# Data_Board_4_Panel.net
KiCad netlist of a schematic drawn in EAGLE
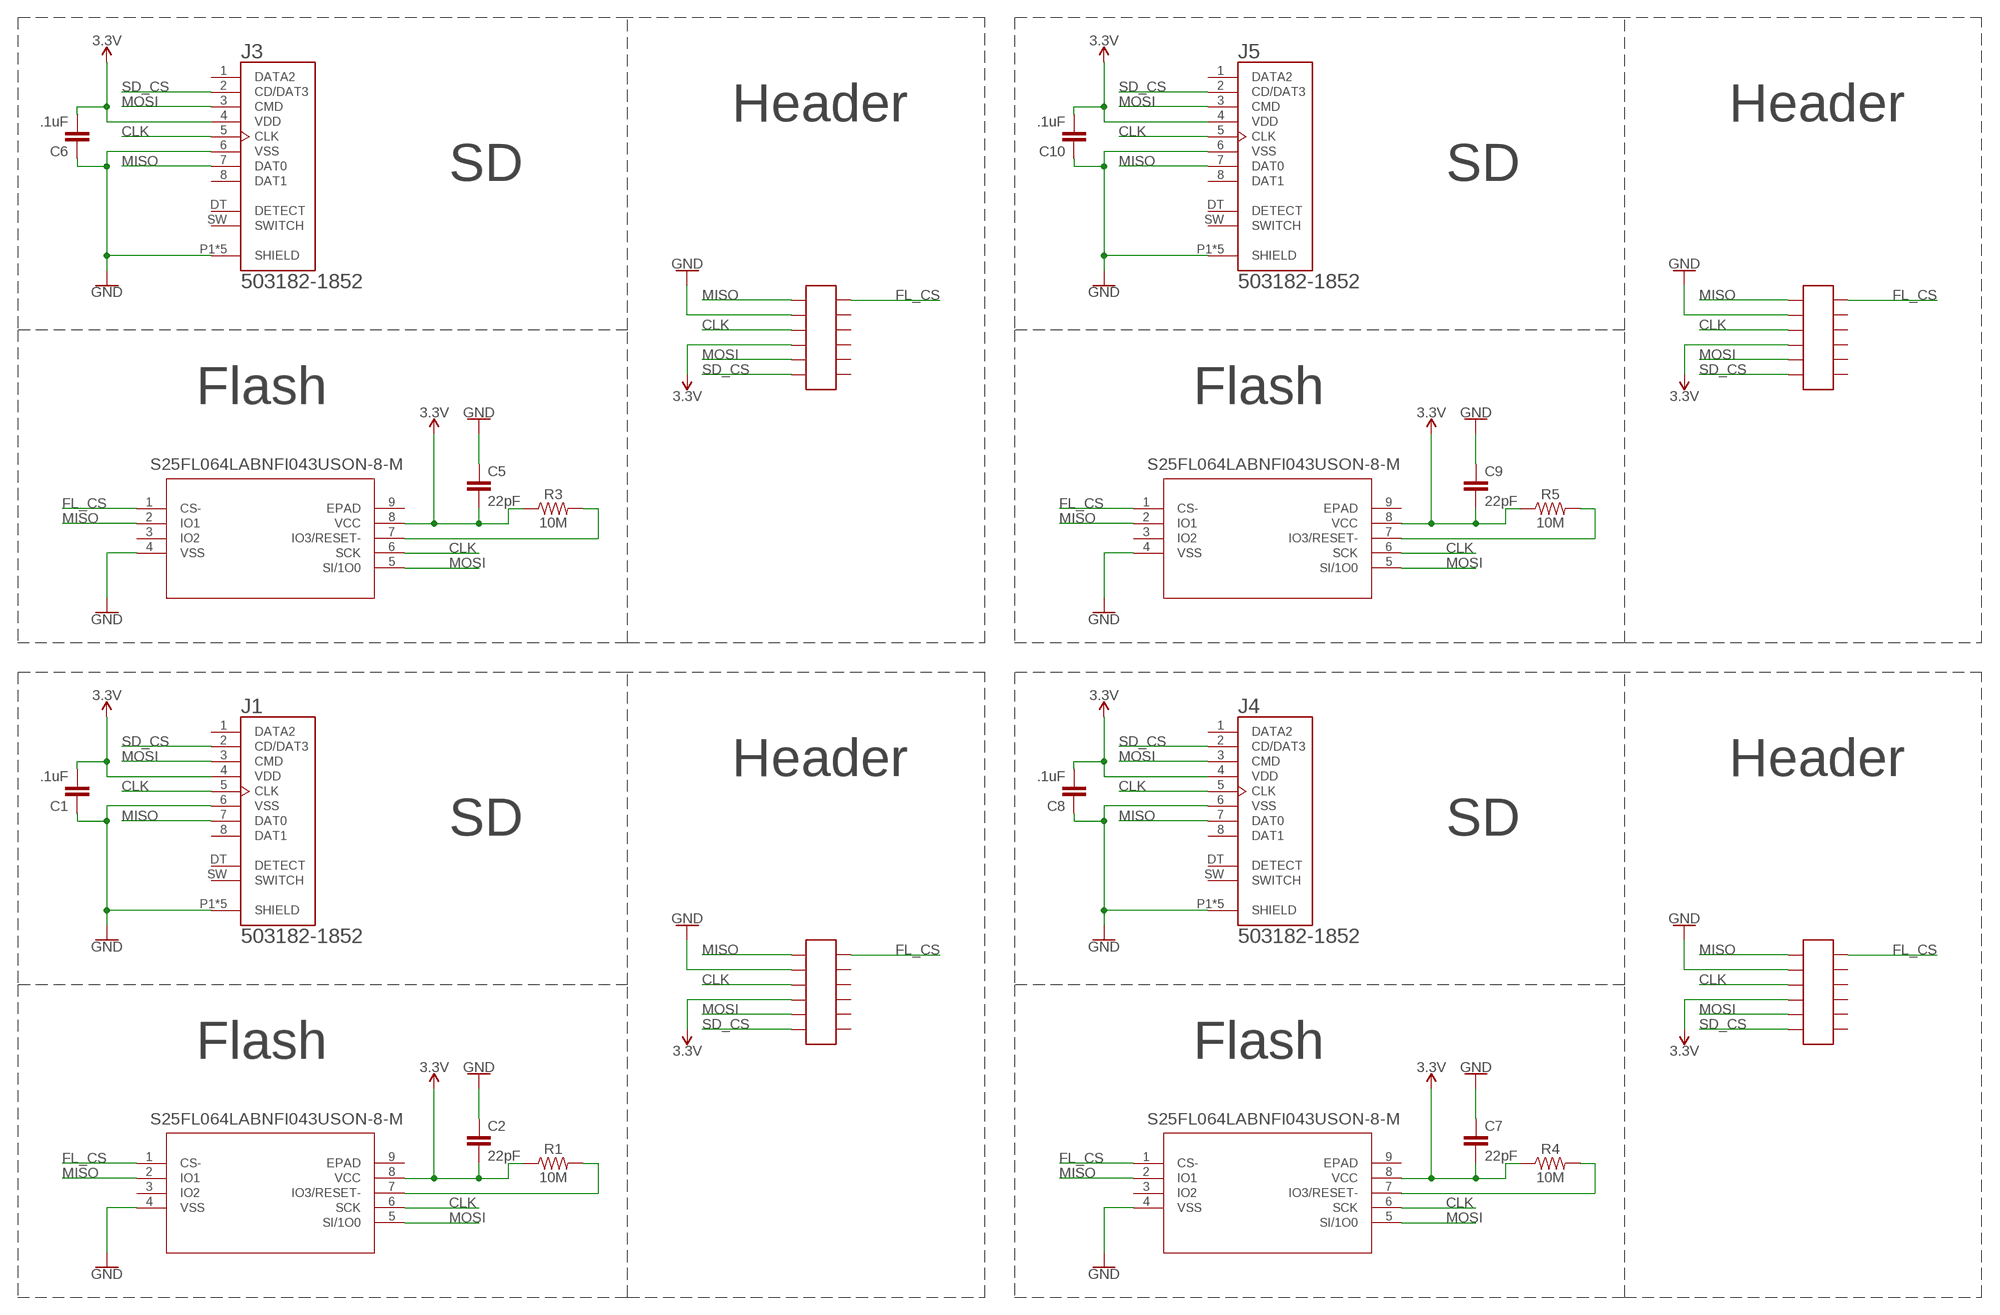
[diagram p0: schematic, sheet 1]

(export (version "E")
  (design (tool "Eeschema 10.0.6"))
  (components
    (comp (ref "C1")
      (value ".1uF")
      (footprint "eagle-import:0603")
      (libsource (lib "eagle-import") (part "10NF-0603-50V-10%"))
    )
    (comp (ref "C2")
      (value "22pF")
      (footprint "eagle-import:0603")
      (libsource (lib "eagle-import") (part "10NF-0603-50V-10%"))
    )
    (comp (ref "C5")
      (value "22pF")
      (footprint "eagle-import:0603")
      (libsource (lib "eagle-import") (part "10NF-0603-50V-10%"))
    )
    (comp (ref "C6")
      (value ".1uF")
      (footprint "eagle-import:0603")
      (libsource (lib "eagle-import") (part "10NF-0603-50V-10%"))
    )
    (comp (ref "C7")
      (value "22pF")
      (footprint "eagle-import:0603")
      (libsource (lib "eagle-import") (part "10NF-0603-50V-10%"))
    )
    (comp (ref "C8")
      (value ".1uF")
      (footprint "eagle-import:0603")
      (libsource (lib "eagle-import") (part "10NF-0603-50V-10%"))
    )
    (comp (ref "C9")
      (value "22pF")
      (footprint "eagle-import:0603")
      (libsource (lib "eagle-import") (part "10NF-0603-50V-10%"))
    )
    (comp (ref "C10")
      (value ".1uF")
      (footprint "eagle-import:0603")
      (libsource (lib "eagle-import") (part "10NF-0603-50V-10%"))
    )
    (comp (ref "J1")
      (value "503182-1852")
      (footprint "eagle-import:MOLEX_503182-1852")
      (fields
        (field (name "DIGI-KEY_PART_NUMBER") "WM12834CT-ND")
        (field (name "MF") "Molex")
        (field (name "MP") "5031821852")
      )
      (libsource (lib "eagle-import") (part "503182-1852"))
    )
    (comp (ref "J3")
      (value "503182-1852")
      (footprint "eagle-import:MOLEX_503182-1852")
      (fields
        (field (name "DIGI-KEY_PART_NUMBER") "WM12834CT-ND")
        (field (name "MF") "Molex")
        (field (name "MP") "5031821852")
      )
      (libsource (lib "eagle-import") (part "503182-1852"))
    )
    (comp (ref "J4")
      (value "503182-1852")
      (footprint "eagle-import:MOLEX_503182-1852")
      (fields
        (field (name "DIGI-KEY_PART_NUMBER") "WM12834CT-ND")
        (field (name "MF") "Molex")
        (field (name "MP") "5031821852")
      )
      (libsource (lib "eagle-import") (part "503182-1852"))
    )
    (comp (ref "J5")
      (value "503182-1852")
      (footprint "eagle-import:MOLEX_503182-1852")
      (fields
        (field (name "DIGI-KEY_PART_NUMBER") "WM12834CT-ND")
        (field (name "MF") "Molex")
        (field (name "MP") "5031821852")
      )
      (libsource (lib "eagle-import") (part "503182-1852"))
    )
    (comp (ref "R1")
      (value "10M")
      (footprint "eagle-import:0603")
      (libsource (lib "eagle-import") (part "220KOHM-0603-1/10W-1%"))
    )
    (comp (ref "R3")
      (value "10M")
      (footprint "eagle-import:0603")
      (libsource (lib "eagle-import") (part "220KOHM-0603-1/10W-1%"))
    )
    (comp (ref "R4")
      (value "10M")
      (footprint "eagle-import:0603")
      (libsource (lib "eagle-import") (part "220KOHM-0603-1/10W-1%"))
    )
    (comp (ref "R5")
      (value "10M")
      (footprint "eagle-import:0603")
      (libsource (lib "eagle-import") (part "220KOHM-0603-1/10W-1%"))
    )
    (comp (ref "U$1")
      (value "12POS_HEADER")
      (footprint "eagle-import:12POS_HEADER")
      (libsource (lib "eagle-import") (part "12POS_HEADER"))
    )
    (comp (ref "U$3")
      (value "12POS_HEADER")
      (footprint "eagle-import:12POS_HEADER")
      (libsource (lib "eagle-import") (part "12POS_HEADER"))
    )
    (comp (ref "U$4")
      (value "12POS_HEADER")
      (footprint "eagle-import:12POS_HEADER")
      (libsource (lib "eagle-import") (part "12POS_HEADER"))
    )
    (comp (ref "U$5")
      (value "12POS_HEADER")
      (footprint "eagle-import:12POS_HEADER")
      (libsource (lib "eagle-import") (part "12POS_HEADER"))
    )
    (comp (ref "U1")
      (value "S25FL064LABNFI043USON-8-M")
      (footprint "eagle-import:USON-8-M")
      (fields
        (field (name "MANUFACTURER_PART_NUMBER") "S25FL064LABNFI043")
        (field (name "COPYRIGHT") "Copyright (C) 2018 Accelerated Designs. All rights reserved")
      )
      (libsource (lib "eagle-import") (part "S25FL064LABNFI043USON-8-M"))
    )
    (comp (ref "U3")
      (value "S25FL064LABNFI043USON-8-M")
      (footprint "eagle-import:USON-8-M")
      (fields
        (field (name "MANUFACTURER_PART_NUMBER") "S25FL064LABNFI043")
        (field (name "COPYRIGHT") "Copyright (C) 2018 Accelerated Designs. All rights reserved")
      )
      (libsource (lib "eagle-import") (part "S25FL064LABNFI043USON-8-M"))
    )
    (comp (ref "U4")
      (value "S25FL064LABNFI043USON-8-M")
      (footprint "eagle-import:USON-8-M")
      (fields
        (field (name "MANUFACTURER_PART_NUMBER") "S25FL064LABNFI043")
        (field (name "COPYRIGHT") "Copyright (C) 2018 Accelerated Designs. All rights reserved")
      )
      (libsource (lib "eagle-import") (part "S25FL064LABNFI043USON-8-M"))
    )
    (comp (ref "U5")
      (value "S25FL064LABNFI043USON-8-M")
      (footprint "eagle-import:USON-8-M")
      (fields
        (field (name "MANUFACTURER_PART_NUMBER") "S25FL064LABNFI043")
        (field (name "COPYRIGHT") "Copyright (C) 2018 Accelerated Designs. All rights reserved")
      )
      (libsource (lib "eagle-import") (part "S25FL064LABNFI043USON-8-M"))
    )
  )
  (nets
    (net (code "1") (name "/CLK") (class "Default")
      (node (ref "J1") (pin "5") (pinfunction "CLK_5") (pintype "bidirectional"))
      (node (ref "J3") (pin "5") (pinfunction "CLK_5") (pintype "bidirectional"))
      (node (ref "J4") (pin "5") (pinfunction "CLK_5") (pintype "bidirectional"))
      (node (ref "J5") (pin "5") (pinfunction "CLK_5") (pintype "bidirectional"))
      (node (ref "U$1") (pin "P$3") (pinfunction "P$3_P$3") (pintype "bidirectional"))
      (node (ref "U$3") (pin "P$3") (pinfunction "P$3_P$3") (pintype "bidirectional"))
      (node (ref "U$4") (pin "P$3") (pinfunction "P$3_P$3") (pintype "bidirectional"))
      (node (ref "U$5") (pin "P$3") (pinfunction "P$3_P$3") (pintype "bidirectional"))
      (node (ref "U1") (pin "6") (pinfunction "SCK_6") (pintype "passive"))
      (node (ref "U3") (pin "6") (pinfunction "SCK_6") (pintype "passive"))
      (node (ref "U4") (pin "6") (pinfunction "SCK_6") (pintype "passive"))
      (node (ref "U5") (pin "6") (pinfunction "SCK_6") (pintype "passive"))
    )
    (net (code "2") (name "/FL_CS") (class "Default")
      (node (ref "U$1") (pin "P$12") (pinfunction "P$12_P$12") (pintype "bidirectional"))
      (node (ref "U$3") (pin "P$12") (pinfunction "P$12_P$12") (pintype "bidirectional"))
      (node (ref "U$4") (pin "P$12") (pinfunction "P$12_P$12") (pintype "bidirectional"))
      (node (ref "U$5") (pin "P$12") (pinfunction "P$12_P$12") (pintype "bidirectional"))
      (node (ref "U1") (pin "1") (pinfunction "CS-_1") (pintype "passive"))
      (node (ref "U3") (pin "1") (pinfunction "CS-_1") (pintype "passive"))
      (node (ref "U4") (pin "1") (pinfunction "CS-_1") (pintype "passive"))
      (node (ref "U5") (pin "1") (pinfunction "CS-_1") (pintype "passive"))
    )
    (net (code "3") (name "/MISO") (class "Default")
      (node (ref "J1") (pin "7") (pinfunction "DAT0_7") (pintype "bidirectional"))
      (node (ref "J3") (pin "7") (pinfunction "DAT0_7") (pintype "bidirectional"))
      (node (ref "J4") (pin "7") (pinfunction "DAT0_7") (pintype "bidirectional"))
      (node (ref "J5") (pin "7") (pinfunction "DAT0_7") (pintype "bidirectional"))
      (node (ref "U$1") (pin "P$1") (pinfunction "P$1_P$1") (pintype "bidirectional"))
      (node (ref "U$3") (pin "P$1") (pinfunction "P$1_P$1") (pintype "bidirectional"))
      (node (ref "U$4") (pin "P$1") (pinfunction "P$1_P$1") (pintype "bidirectional"))
      (node (ref "U$5") (pin "P$1") (pinfunction "P$1_P$1") (pintype "bidirectional"))
      (node (ref "U1") (pin "2") (pinfunction "IO1_2") (pintype "bidirectional"))
      (node (ref "U3") (pin "2") (pinfunction "IO1_2") (pintype "bidirectional"))
      (node (ref "U4") (pin "2") (pinfunction "IO1_2") (pintype "bidirectional"))
      (node (ref "U5") (pin "2") (pinfunction "IO1_2") (pintype "bidirectional"))
    )
    (net (code "4") (name "/MOSI") (class "Default")
      (node (ref "J1") (pin "3") (pinfunction "CMD_3") (pintype "bidirectional"))
      (node (ref "J3") (pin "3") (pinfunction "CMD_3") (pintype "bidirectional"))
      (node (ref "J4") (pin "3") (pinfunction "CMD_3") (pintype "bidirectional"))
      (node (ref "J5") (pin "3") (pinfunction "CMD_3") (pintype "bidirectional"))
      (node (ref "U$1") (pin "P$5") (pinfunction "P$5_P$5") (pintype "bidirectional"))
      (node (ref "U$3") (pin "P$5") (pinfunction "P$5_P$5") (pintype "bidirectional"))
      (node (ref "U$4") (pin "P$5") (pinfunction "P$5_P$5") (pintype "bidirectional"))
      (node (ref "U$5") (pin "P$5") (pinfunction "P$5_P$5") (pintype "bidirectional"))
      (node (ref "U1") (pin "5") (pinfunction "SI/1O0_5") (pintype "passive"))
      (node (ref "U3") (pin "5") (pinfunction "SI/1O0_5") (pintype "passive"))
      (node (ref "U4") (pin "5") (pinfunction "SI/1O0_5") (pintype "passive"))
      (node (ref "U5") (pin "5") (pinfunction "SI/1O0_5") (pintype "passive"))
    )
    (net (code "5") (name "/SD_CS") (class "Default")
      (node (ref "J1") (pin "2") (pinfunction "CD/DAT3_2") (pintype "bidirectional"))
      (node (ref "J3") (pin "2") (pinfunction "CD/DAT3_2") (pintype "bidirectional"))
      (node (ref "J4") (pin "2") (pinfunction "CD/DAT3_2") (pintype "bidirectional"))
      (node (ref "J5") (pin "2") (pinfunction "CD/DAT3_2") (pintype "bidirectional"))
      (node (ref "U$1") (pin "P$6") (pinfunction "P$6_P$6") (pintype "bidirectional"))
      (node (ref "U$3") (pin "P$6") (pinfunction "P$6_P$6") (pintype "bidirectional"))
      (node (ref "U$4") (pin "P$6") (pinfunction "P$6_P$6") (pintype "bidirectional"))
      (node (ref "U$5") (pin "P$6") (pinfunction "P$6_P$6") (pintype "bidirectional"))
    )
    (net (code "6") (name "3.3V") (class "Default")
      (node (ref "C1") (pin "2") (pinfunction "2_2") (pintype "passive"))
      (node (ref "C10") (pin "2") (pinfunction "2_2") (pintype "passive"))
      (node (ref "C2") (pin "2") (pinfunction "2_2") (pintype "passive"))
      (node (ref "C5") (pin "2") (pinfunction "2_2") (pintype "passive"))
      (node (ref "C6") (pin "2") (pinfunction "2_2") (pintype "passive"))
      (node (ref "C7") (pin "2") (pinfunction "2_2") (pintype "passive"))
      (node (ref "C8") (pin "2") (pinfunction "2_2") (pintype "passive"))
      (node (ref "C9") (pin "2") (pinfunction "2_2") (pintype "passive"))
      (node (ref "J1") (pin "4") (pinfunction "VDD_4") (pintype "power_in"))
      (node (ref "J3") (pin "4") (pinfunction "VDD_4") (pintype "power_in"))
      (node (ref "J4") (pin "4") (pinfunction "VDD_4") (pintype "power_in"))
      (node (ref "J5") (pin "4") (pinfunction "VDD_4") (pintype "power_in"))
      (node (ref "R1") (pin "1") (pinfunction "1_1") (pintype "passive"))
      (node (ref "R3") (pin "1") (pinfunction "1_1") (pintype "passive"))
      (node (ref "R4") (pin "1") (pinfunction "1_1") (pintype "passive"))
      (node (ref "R5") (pin "1") (pinfunction "1_1") (pintype "passive"))
      (node (ref "U$1") (pin "P$4") (pinfunction "P$4_P$4") (pintype "bidirectional"))
      (node (ref "U$3") (pin "P$4") (pinfunction "P$4_P$4") (pintype "bidirectional"))
      (node (ref "U$4") (pin "P$4") (pinfunction "P$4_P$4") (pintype "bidirectional"))
      (node (ref "U$5") (pin "P$4") (pinfunction "P$4_P$4") (pintype "bidirectional"))
      (node (ref "U1") (pin "8") (pinfunction "VCC_8") (pintype "power_in"))
      (node (ref "U3") (pin "8") (pinfunction "VCC_8") (pintype "power_in"))
      (node (ref "U4") (pin "8") (pinfunction "VCC_8") (pintype "power_in"))
      (node (ref "U5") (pin "8") (pinfunction "VCC_8") (pintype "power_in"))
    )
    (net (code "7") (name "GND") (class "Default")
      (node (ref "C1") (pin "1") (pinfunction "1_1") (pintype "passive"))
      (node (ref "C10") (pin "1") (pinfunction "1_1") (pintype "passive"))
      (node (ref "C2") (pin "1") (pinfunction "1_1") (pintype "passive"))
      (node (ref "C5") (pin "1") (pinfunction "1_1") (pintype "passive"))
      (node (ref "C6") (pin "1") (pinfunction "1_1") (pintype "passive"))
      (node (ref "C7") (pin "1") (pinfunction "1_1") (pintype "passive"))
      (node (ref "C8") (pin "1") (pinfunction "1_1") (pintype "passive"))
      (node (ref "C9") (pin "1") (pinfunction "1_1") (pintype "passive"))
      (node (ref "J1") (pin "6") (pinfunction "VSS_6") (pintype "power_in"))
      (node (ref "J1") (pin "P1") (pinfunction "SHIELD_P1") (pintype "passive"))
      (node (ref "J1") (pin "P2") (pinfunction "SHIELD_P2") (pintype "passive"))
      (node (ref "J1") (pin "P3") (pinfunction "SHIELD_P3") (pintype "passive"))
      (node (ref "J1") (pin "P4") (pinfunction "SHIELD_P4") (pintype "passive"))
      (node (ref "J1") (pin "P5") (pinfunction "SHIELD_P5") (pintype "passive"))
      (node (ref "J3") (pin "6") (pinfunction "VSS_6") (pintype "power_in"))
      (node (ref "J3") (pin "P1") (pinfunction "SHIELD_P1") (pintype "passive"))
      (node (ref "J3") (pin "P2") (pinfunction "SHIELD_P2") (pintype "passive"))
      (node (ref "J3") (pin "P3") (pinfunction "SHIELD_P3") (pintype "passive"))
      (node (ref "J3") (pin "P4") (pinfunction "SHIELD_P4") (pintype "passive"))
      (node (ref "J3") (pin "P5") (pinfunction "SHIELD_P5") (pintype "passive"))
      (node (ref "J4") (pin "6") (pinfunction "VSS_6") (pintype "power_in"))
      (node (ref "J4") (pin "P1") (pinfunction "SHIELD_P1") (pintype "passive"))
      (node (ref "J4") (pin "P2") (pinfunction "SHIELD_P2") (pintype "passive"))
      (node (ref "J4") (pin "P3") (pinfunction "SHIELD_P3") (pintype "passive"))
      (node (ref "J4") (pin "P4") (pinfunction "SHIELD_P4") (pintype "passive"))
      (node (ref "J4") (pin "P5") (pinfunction "SHIELD_P5") (pintype "passive"))
      (node (ref "J5") (pin "6") (pinfunction "VSS_6") (pintype "power_in"))
      (node (ref "J5") (pin "P1") (pinfunction "SHIELD_P1") (pintype "passive"))
      (node (ref "J5") (pin "P2") (pinfunction "SHIELD_P2") (pintype "passive"))
      (node (ref "J5") (pin "P3") (pinfunction "SHIELD_P3") (pintype "passive"))
      (node (ref "J5") (pin "P4") (pinfunction "SHIELD_P4") (pintype "passive"))
      (node (ref "J5") (pin "P5") (pinfunction "SHIELD_P5") (pintype "passive"))
      (node (ref "U$1") (pin "P$2") (pinfunction "P$2_P$2") (pintype "bidirectional"))
      (node (ref "U$3") (pin "P$2") (pinfunction "P$2_P$2") (pintype "bidirectional"))
      (node (ref "U$4") (pin "P$2") (pinfunction "P$2_P$2") (pintype "bidirectional"))
      (node (ref "U$5") (pin "P$2") (pinfunction "P$2_P$2") (pintype "bidirectional"))
      (node (ref "U1") (pin "4") (pinfunction "VSS_4") (pintype "passive"))
      (node (ref "U3") (pin "4") (pinfunction "VSS_4") (pintype "passive"))
      (node (ref "U4") (pin "4") (pinfunction "VSS_4") (pintype "passive"))
      (node (ref "U5") (pin "4") (pinfunction "VSS_4") (pintype "passive"))
    )
    (net (code "8") (name "Net-(U1-IO3{slash}RESET-)") (class "Default")
      (node (ref "R1") (pin "2") (pinfunction "2_2") (pintype "passive"))
      (node (ref "U1") (pin "7") (pinfunction "IO3/RESET-_7") (pintype "bidirectional"))
    )
    (net (code "9") (name "Net-(U3-IO3{slash}RESET-)") (class "Default")
      (node (ref "R3") (pin "2") (pinfunction "2_2") (pintype "passive"))
      (node (ref "U3") (pin "7") (pinfunction "IO3/RESET-_7") (pintype "bidirectional"))
    )
    (net (code "10") (name "Net-(U4-IO3{slash}RESET-)") (class "Default")
      (node (ref "R4") (pin "2") (pinfunction "2_2") (pintype "passive"))
      (node (ref "U4") (pin "7") (pinfunction "IO3/RESET-_7") (pintype "bidirectional"))
    )
    (net (code "11") (name "Net-(U5-IO3{slash}RESET-)") (class "Default")
      (node (ref "R5") (pin "2") (pinfunction "2_2") (pintype "passive"))
      (node (ref "U5") (pin "7") (pinfunction "IO3/RESET-_7") (pintype "bidirectional"))
    )
    (net (code "12") (name "unconnected-(J1-DAT1-Pad8)") (class "Default")
      (node (ref "J1") (pin "8") (pinfunction "DAT1_8") (pintype "bidirectional"))
    )
    (net (code "13") (name "unconnected-(J1-DATA2-Pad1)") (class "Default")
      (node (ref "J1") (pin "1") (pinfunction "DATA2_1") (pintype "bidirectional"))
    )
    (net (code "14") (name "unconnected-(J1-DETECT-PadDT)") (class "Default")
      (node (ref "J1") (pin "DT") (pinfunction "DETECT_DT") (pintype "bidirectional"))
    )
    (net (code "15") (name "unconnected-(J1-SWITCH-PadSW)") (class "Default")
      (node (ref "J1") (pin "SW") (pinfunction "SWITCH_SW") (pintype "bidirectional"))
    )
    (net (code "16") (name "unconnected-(J3-DAT1-Pad8)") (class "Default")
      (node (ref "J3") (pin "8") (pinfunction "DAT1_8") (pintype "bidirectional"))
    )
    (net (code "17") (name "unconnected-(J3-DATA2-Pad1)") (class "Default")
      (node (ref "J3") (pin "1") (pinfunction "DATA2_1") (pintype "bidirectional"))
    )
    (net (code "18") (name "unconnected-(J3-DETECT-PadDT)") (class "Default")
      (node (ref "J3") (pin "DT") (pinfunction "DETECT_DT") (pintype "bidirectional"))
    )
    (net (code "19") (name "unconnected-(J3-SWITCH-PadSW)") (class "Default")
      (node (ref "J3") (pin "SW") (pinfunction "SWITCH_SW") (pintype "bidirectional"))
    )
    (net (code "20") (name "unconnected-(J4-DAT1-Pad8)") (class "Default")
      (node (ref "J4") (pin "8") (pinfunction "DAT1_8") (pintype "bidirectional"))
    )
    (net (code "21") (name "unconnected-(J4-DATA2-Pad1)") (class "Default")
      (node (ref "J4") (pin "1") (pinfunction "DATA2_1") (pintype "bidirectional"))
    )
    (net (code "22") (name "unconnected-(J4-DETECT-PadDT)") (class "Default")
      (node (ref "J4") (pin "DT") (pinfunction "DETECT_DT") (pintype "bidirectional"))
    )
    (net (code "23") (name "unconnected-(J4-SWITCH-PadSW)") (class "Default")
      (node (ref "J4") (pin "SW") (pinfunction "SWITCH_SW") (pintype "bidirectional"))
    )
    (net (code "24") (name "unconnected-(J5-DAT1-Pad8)") (class "Default")
      (node (ref "J5") (pin "8") (pinfunction "DAT1_8") (pintype "bidirectional"))
    )
    (net (code "25") (name "unconnected-(J5-DATA2-Pad1)") (class "Default")
      (node (ref "J5") (pin "1") (pinfunction "DATA2_1") (pintype "bidirectional"))
    )
    (net (code "26") (name "unconnected-(J5-DETECT-PadDT)") (class "Default")
      (node (ref "J5") (pin "DT") (pinfunction "DETECT_DT") (pintype "bidirectional"))
    )
    (net (code "27") (name "unconnected-(J5-SWITCH-PadSW)") (class "Default")
      (node (ref "J5") (pin "SW") (pinfunction "SWITCH_SW") (pintype "bidirectional"))
    )
    (net (code "28") (name "unconnected-(U$1-PadP$7)") (class "Default")
      (node (ref "U$1") (pin "P$7") (pinfunction "P$7_P$7") (pintype "bidirectional"))
    )
    (net (code "29") (name "unconnected-(U$1-PadP$8)") (class "Default")
      (node (ref "U$1") (pin "P$8") (pinfunction "P$8_P$8") (pintype "bidirectional"))
    )
    (net (code "30") (name "unconnected-(U$1-PadP$9)") (class "Default")
      (node (ref "U$1") (pin "P$9") (pinfunction "P$9_P$9") (pintype "bidirectional"))
    )
    (net (code "31") (name "unconnected-(U$1-PadP$10)") (class "Default")
      (node (ref "U$1") (pin "P$10") (pinfunction "P$10_P$10") (pintype "bidirectional"))
    )
    (net (code "32") (name "unconnected-(U$1-PadP$11)") (class "Default")
      (node (ref "U$1") (pin "P$11") (pinfunction "P$11_P$11") (pintype "bidirectional"))
    )
    (net (code "33") (name "unconnected-(U$3-PadP$7)") (class "Default")
      (node (ref "U$3") (pin "P$7") (pinfunction "P$7_P$7") (pintype "bidirectional"))
    )
    (net (code "34") (name "unconnected-(U$3-PadP$8)") (class "Default")
      (node (ref "U$3") (pin "P$8") (pinfunction "P$8_P$8") (pintype "bidirectional"))
    )
    (net (code "35") (name "unconnected-(U$3-PadP$9)") (class "Default")
      (node (ref "U$3") (pin "P$9") (pinfunction "P$9_P$9") (pintype "bidirectional"))
    )
    (net (code "36") (name "unconnected-(U$3-PadP$10)") (class "Default")
      (node (ref "U$3") (pin "P$10") (pinfunction "P$10_P$10") (pintype "bidirectional"))
    )
    (net (code "37") (name "unconnected-(U$3-PadP$11)") (class "Default")
      (node (ref "U$3") (pin "P$11") (pinfunction "P$11_P$11") (pintype "bidirectional"))
    )
    (net (code "38") (name "unconnected-(U$4-PadP$7)") (class "Default")
      (node (ref "U$4") (pin "P$7") (pinfunction "P$7_P$7") (pintype "bidirectional"))
    )
    (net (code "39") (name "unconnected-(U$4-PadP$8)") (class "Default")
      (node (ref "U$4") (pin "P$8") (pinfunction "P$8_P$8") (pintype "bidirectional"))
    )
    (net (code "40") (name "unconnected-(U$4-PadP$9)") (class "Default")
      (node (ref "U$4") (pin "P$9") (pinfunction "P$9_P$9") (pintype "bidirectional"))
    )
    (net (code "41") (name "unconnected-(U$4-PadP$10)") (class "Default")
      (node (ref "U$4") (pin "P$10") (pinfunction "P$10_P$10") (pintype "bidirectional"))
    )
    (net (code "42") (name "unconnected-(U$4-PadP$11)") (class "Default")
      (node (ref "U$4") (pin "P$11") (pinfunction "P$11_P$11") (pintype "bidirectional"))
    )
    (net (code "43") (name "unconnected-(U$5-PadP$7)") (class "Default")
      (node (ref "U$5") (pin "P$7") (pinfunction "P$7_P$7") (pintype "bidirectional"))
    )
    (net (code "44") (name "unconnected-(U$5-PadP$8)") (class "Default")
      (node (ref "U$5") (pin "P$8") (pinfunction "P$8_P$8") (pintype "bidirectional"))
    )
    (net (code "45") (name "unconnected-(U$5-PadP$9)") (class "Default")
      (node (ref "U$5") (pin "P$9") (pinfunction "P$9_P$9") (pintype "bidirectional"))
    )
    (net (code "46") (name "unconnected-(U$5-PadP$10)") (class "Default")
      (node (ref "U$5") (pin "P$10") (pinfunction "P$10_P$10") (pintype "bidirectional"))
    )
    (net (code "47") (name "unconnected-(U$5-PadP$11)") (class "Default")
      (node (ref "U$5") (pin "P$11") (pinfunction "P$11_P$11") (pintype "bidirectional"))
    )
    (net (code "48") (name "unconnected-(U1-EPAD-Pad9)") (class "Default")
      (node (ref "U1") (pin "9") (pinfunction "EPAD_9") (pintype "passive"))
    )
    (net (code "49") (name "unconnected-(U1-IO2-Pad3)") (class "Default")
      (node (ref "U1") (pin "3") (pinfunction "IO2_3") (pintype "bidirectional"))
    )
    (net (code "50") (name "unconnected-(U3-EPAD-Pad9)") (class "Default")
      (node (ref "U3") (pin "9") (pinfunction "EPAD_9") (pintype "passive"))
    )
    (net (code "51") (name "unconnected-(U3-IO2-Pad3)") (class "Default")
      (node (ref "U3") (pin "3") (pinfunction "IO2_3") (pintype "bidirectional"))
    )
    (net (code "52") (name "unconnected-(U4-EPAD-Pad9)") (class "Default")
      (node (ref "U4") (pin "9") (pinfunction "EPAD_9") (pintype "passive"))
    )
    (net (code "53") (name "unconnected-(U4-IO2-Pad3)") (class "Default")
      (node (ref "U4") (pin "3") (pinfunction "IO2_3") (pintype "bidirectional"))
    )
    (net (code "54") (name "unconnected-(U5-EPAD-Pad9)") (class "Default")
      (node (ref "U5") (pin "9") (pinfunction "EPAD_9") (pintype "passive"))
    )
    (net (code "55") (name "unconnected-(U5-IO2-Pad3)") (class "Default")
      (node (ref "U5") (pin "3") (pinfunction "IO2_3") (pintype "bidirectional"))
    )
  )
)
